# webUSB_V2_combined.net
KiCad netlist of a schematic drawn in EAGLE
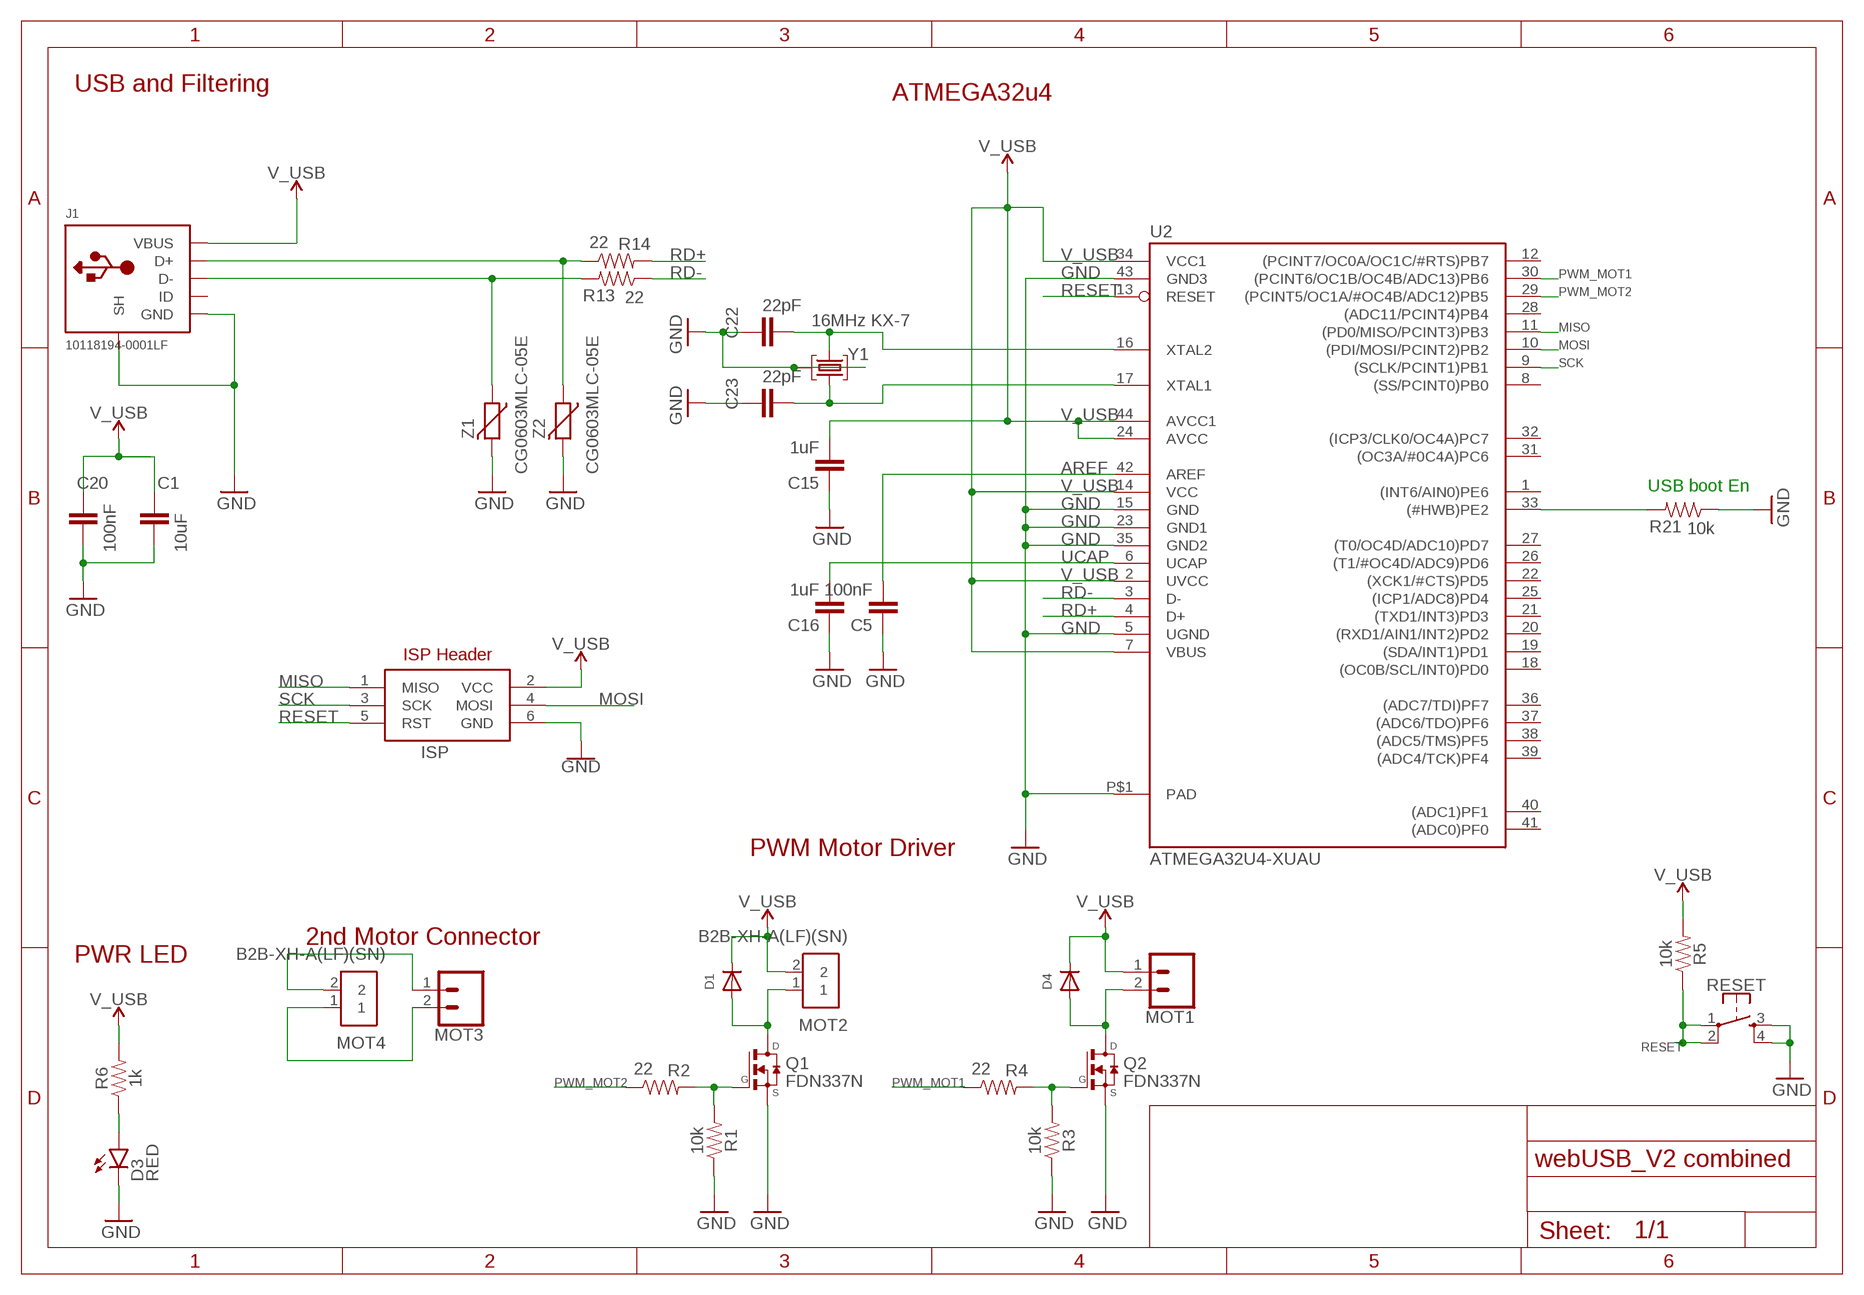
[diagram p0: schematic, sheet 1]

(export (version "E")
  (design (tool "Eeschema 10.0.6"))
  (components
    (comp (ref "C1")
      (value "10uF")
      (footprint "eagle-import:C0805")
      (libsource (lib "eagle-import") (part "CAPACITORSC0805"))
    )
    (comp (ref "C5")
      (value "100nF")
      (footprint "eagle-import:C0603")
      (libsource (lib "eagle-import") (part "My-custom-components_5707583_CAPACITORSC0603"))
    )
    (comp (ref "C15")
      (value "1uF")
      (footprint "eagle-import:C0603")
      (libsource (lib "eagle-import") (part "My-custom-components_5707583_CAPACITORSC0603"))
    )
    (comp (ref "C16")
      (value "1uF")
      (footprint "eagle-import:C0603")
      (libsource (lib "eagle-import") (part "My-custom-components_5707583_CAPACITORSC0603"))
    )
    (comp (ref "C20")
      (value "100nF")
      (footprint "eagle-import:C0603")
      (libsource (lib "eagle-import") (part "CAPACITORSC0603"))
    )
    (comp (ref "C22")
      (value "22pF")
      (footprint "eagle-import:C0603")
      (libsource (lib "eagle-import") (part "My-custom-components_5707583_CAPACITORSC0603"))
    )
    (comp (ref "C23")
      (value "22pF")
      (footprint "eagle-import:C0603")
      (libsource (lib "eagle-import") (part "My-custom-components_5707583_CAPACITORSC0603"))
    )
    (comp (ref "D1")
      (value "DIODESOD-123")
      (footprint "eagle-import:SOD-123")
      (libsource (lib "eagle-import") (part "DIODESOD-123"))
    )
    (comp (ref "D3")
      (value "RED")
      (footprint "eagle-import:LED-0603")
      (libsource (lib "eagle-import") (part "LED-RED0603"))
    )
    (comp (ref "D4")
      (value "DIODESOD-123")
      (footprint "eagle-import:SOD-123")
      (libsource (lib "eagle-import") (part "DIODESOD-123"))
    )
    (comp (ref "ISP")
      (value "AVRISP-6")
      (footprint "eagle-import:AVRISP")
      (libsource (lib "eagle-import") (part "AVRISP-6"))
    )
    (comp (ref "J1")
      (value "10118194-0001LF")
      (footprint "eagle-import:FRAMATOME_10118194-0001LF")
      (fields (field (name "MF") "Amphenol"))
      (libsource (lib "eagle-import") (part "10118194-0001LF"))
    )
    (comp (ref "MOT1")
      (value "CONN_02")
      (footprint "eagle-import:1X02")
      (libsource (lib "eagle-import") (part "CONN_02"))
    )
    (comp (ref "MOT2")
      (value "B2B-XH-A(LF)(SN)")
      (footprint "eagle-import:SHDR2W64P0X250_1X2_740X575X700")
      (fields (field (name "RS_PART_NUMBER") "1667312"))
      (libsource (lib "eagle-import") (part "B2B-XH-A(LF)(SN)"))
    )
    (comp (ref "MOT3")
      (value "CONN_02")
      (footprint "eagle-import:1X02")
      (libsource (lib "eagle-import") (part "CONN_02"))
    )
    (comp (ref "MOT4")
      (value "B2B-XH-A(LF)(SN)")
      (footprint "eagle-import:SHDR2W64P0X250_1X2_740X575X700")
      (fields (field (name "RS_PART_NUMBER") "1667312"))
      (libsource (lib "eagle-import") (part "B2B-XH-A(LF)(SN)"))
    )
    (comp (ref "Q1")
      (value "FDN337N")
      (footprint "eagle-import:SSOT-3")
      (fields (field (name "MF") "ON Semiconductor"))
      (libsource (lib "eagle-import") (part "FDN337N"))
    )
    (comp (ref "Q2")
      (value "FDN337N")
      (footprint "eagle-import:SSOT-3")
      (fields (field (name "MF") "ON Semiconductor"))
      (libsource (lib "eagle-import") (part "FDN337N"))
    )
    (comp (ref "R1")
      (value "10k")
      (footprint "eagle-import:R0603")
      (libsource (lib "eagle-import") (part "RESISTORSR0603"))
    )
    (comp (ref "R2")
      (value "22")
      (footprint "eagle-import:R0603")
      (libsource (lib "eagle-import") (part "RESISTORSR0603"))
    )
    (comp (ref "R3")
      (value "10k")
      (footprint "eagle-import:R0603")
      (libsource (lib "eagle-import") (part "RESISTORSR0603"))
    )
    (comp (ref "R4")
      (value "22")
      (footprint "eagle-import:R0603")
      (libsource (lib "eagle-import") (part "RESISTORSR0603"))
    )
    (comp (ref "R5")
      (value "10k")
      (footprint "eagle-import:R0603")
      (libsource (lib "eagle-import") (part "RESISTORSR0603"))
    )
    (comp (ref "R6")
      (value "1k")
      (footprint "eagle-import:R0603")
      (libsource (lib "eagle-import") (part "RESISTORSR0603"))
    )
    (comp (ref "R13")
      (value "22")
      (footprint "eagle-import:R0603")
      (libsource (lib "eagle-import") (part "RESISTORSR0603"))
    )
    (comp (ref "R14")
      (value "22")
      (footprint "eagle-import:R0603")
      (libsource (lib "eagle-import") (part "RESISTORSR0603"))
    )
    (comp (ref "R21")
      (value "10k")
      (footprint "eagle-import:R0603")
      (libsource (lib "eagle-import") (part "My-custom-components_5707583_RESISTORSR0603"))
    )
    (comp (ref "RESET")
      (value "TACTILE_BUTTON_PTS810")
      (footprint "eagle-import:PTS810")
      (libsource (lib "eagle-import") (part "TACTILE_BUTTON_PTS810"))
    )
    (comp (ref "U2")
      (value "ATMEGA32U4-XUAU")
      (footprint "eagle-import:TQFP44-PAD")
      (libsource (lib "eagle-import") (part "ATMEGA32U4-XUAU"))
    )
    (comp (ref "Y1")
      (value "16MHz KX-7")
      (footprint "eagle-import:CRYSTAL-3.2-2.5")
      (libsource (lib "eagle-import") (part "CRYSTAL-3.2-2.5"))
    )
    (comp (ref "Z1")
      (value "CG0603MLC-05E")
      (footprint "eagle-import:CT_CN0603")
      (libsource (lib "eagle-import") (part "VARISTORCN0603"))
    )
    (comp (ref "Z2")
      (value "CG0603MLC-05E")
      (footprint "eagle-import:CT_CN0603")
      (libsource (lib "eagle-import") (part "VARISTORCN0603"))
    )
  )
  (nets
    (net (code "1") (name "/AREF") (class "Default")
      (node (ref "C5") (pin "2") (pinfunction "2_2") (pintype "passive"))
      (node (ref "U2") (pin "42") (pinfunction "AREF_42") (pintype "power_in"))
    )
    (net (code "2") (name "/RD+") (class "Default")
      (node (ref "R14") (pin "2") (pinfunction "2_2") (pintype "passive"))
      (node (ref "U2") (pin "4") (pinfunction "D+_4") (pintype "bidirectional"))
    )
    (net (code "3") (name "/RD-") (class "Default")
      (node (ref "R13") (pin "1") (pinfunction "1_1") (pintype "passive"))
      (node (ref "U2") (pin "3") (pinfunction "D-_3") (pintype "bidirectional"))
    )
    (net (code "4") (name "/UCAP") (class "Default")
      (node (ref "C16") (pin "2") (pinfunction "2_2") (pintype "passive"))
      (node (ref "U2") (pin "6") (pinfunction "UCAP_6") (pintype "passive"))
    )
    (net (code "5") (name "GND") (class "Default")
      (node (ref "C1") (pin "1") (pinfunction "1_1") (pintype "passive"))
      (node (ref "C15") (pin "1") (pinfunction "1_1") (pintype "passive"))
      (node (ref "C16") (pin "1") (pinfunction "1_1") (pintype "passive"))
      (node (ref "C20") (pin "1") (pinfunction "1_1") (pintype "passive"))
      (node (ref "C22") (pin "2") (pinfunction "2_2") (pintype "passive"))
      (node (ref "C23") (pin "2") (pinfunction "2_2") (pintype "passive"))
      (node (ref "C5") (pin "1") (pinfunction "1_1") (pintype "passive"))
      (node (ref "D3") (pin "C") (pinfunction "C_C") (pintype "passive"))
      (node (ref "ISP") (pin "6") (pinfunction "GND_6") (pintype "power_in"))
      (node (ref "J1") (pin "GND") (pinfunction "GND_GND") (pintype "power_in"))
      (node (ref "J1") (pin "SH1") (pinfunction "SH_SH1") (pintype "power_in"))
      (node (ref "J1") (pin "SH2") (pinfunction "SH_SH2") (pintype "power_in"))
      (node (ref "J1") (pin "SH3") (pinfunction "SH_SH3") (pintype "power_in"))
      (node (ref "J1") (pin "SH4") (pinfunction "SH_SH4") (pintype "power_in"))
      (node (ref "J1") (pin "SH5") (pinfunction "SH_SH5") (pintype "power_in"))
      (node (ref "J1") (pin "SH6") (pinfunction "SH_SH6") (pintype "power_in"))
      (node (ref "J1") (pin "SH7") (pinfunction "SH_SH7") (pintype "power_in"))
      (node (ref "J1") (pin "SH8") (pinfunction "SH_SH8") (pintype "power_in"))
      (node (ref "Q1") (pin "2") (pinfunction "S_2") (pintype "passive"))
      (node (ref "Q2") (pin "2") (pinfunction "S_2") (pintype "passive"))
      (node (ref "R1") (pin "1") (pinfunction "1_1") (pintype "passive"))
      (node (ref "R21") (pin "1") (pinfunction "1_1") (pintype "passive"))
      (node (ref "R3") (pin "1") (pinfunction "1_1") (pintype "passive"))
      (node (ref "RESET") (pin "3") (pinfunction "3_3") (pintype "passive"))
      (node (ref "RESET") (pin "4") (pinfunction "4_4") (pintype "passive"))
      (node (ref "U2") (pin "15") (pinfunction "GND_15") (pintype "power_in"))
      (node (ref "U2") (pin "23") (pinfunction "GND1_23") (pintype "power_in"))
      (node (ref "U2") (pin "35") (pinfunction "GND2_35") (pintype "power_in"))
      (node (ref "U2") (pin "43") (pinfunction "GND3_43") (pintype "power_in"))
      (node (ref "U2") (pin "5") (pinfunction "UGND_5") (pintype "power_in"))
      (node (ref "U2") (pin "P$1") (pinfunction "PAD_P$1") (pintype "power_in"))
      (node (ref "Y1") (pin "2") (pinfunction "GND_2") (pintype "passive"))
      (node (ref "Y1") (pin "4") (pinfunction "GND_4") (pintype "passive"))
      (node (ref "Z1") (pin "2") (pinfunction "2_2") (pintype "passive"))
      (node (ref "Z2") (pin "2") (pinfunction "2_2") (pintype "passive"))
    )
    (net (code "6") (name "MISO") (class "Default")
      (node (ref "ISP") (pin "1") (pinfunction "MISO_1") (pintype "input"))
      (node (ref "U2") (pin "11") (pinfunction "(PD0/MISO/PCINT3)PB3_11") (pintype "bidirectional"))
    )
    (net (code "7") (name "MOSI") (class "Default")
      (node (ref "ISP") (pin "4") (pinfunction "MOSI_4") (pintype "output"))
      (node (ref "U2") (pin "10") (pinfunction "(PDI/MOSI/PCINT2)PB2_10") (pintype "bidirectional"))
    )
    (net (code "8") (name "Net-(D3-PadA)") (class "Default")
      (node (ref "D3") (pin "A") (pinfunction "A_A") (pintype "passive"))
      (node (ref "R6") (pin "1") (pinfunction "1_1") (pintype "passive"))
    )
    (net (code "9") (name "Net-(J1-PadD+)") (class "Default")
      (node (ref "J1") (pin "D+") (pinfunction "D+_D+") (pintype "bidirectional"))
      (node (ref "R14") (pin "1") (pinfunction "1_1") (pintype "passive"))
      (node (ref "Z2") (pin "1") (pinfunction "1_1") (pintype "passive"))
    )
    (net (code "10") (name "Net-(J1-PadD-)") (class "Default")
      (node (ref "J1") (pin "D-") (pinfunction "D-_D-") (pintype "bidirectional"))
      (node (ref "R13") (pin "2") (pinfunction "2_2") (pintype "passive"))
      (node (ref "Z1") (pin "1") (pinfunction "1_1") (pintype "passive"))
    )
    (net (code "11") (name "Net-(MOT3-Pad1)") (class "Default")
      (node (ref "MOT3") (pin "1") (pinfunction "1_1") (pintype "passive"))
      (node (ref "MOT4") (pin "2") (pinfunction "2_2") (pintype "bidirectional"))
    )
    (net (code "12") (name "Net-(MOT3-Pad2)") (class "Default")
      (node (ref "MOT3") (pin "2") (pinfunction "2_2") (pintype "passive"))
      (node (ref "MOT4") (pin "1") (pinfunction "1_1") (pintype "bidirectional"))
    )
    (net (code "13") (name "Net-(Q1-D)") (class "Default")
      (node (ref "D1") (pin "A") (pinfunction "A_A") (pintype "passive"))
      (node (ref "MOT2") (pin "1") (pinfunction "1_1") (pintype "bidirectional"))
      (node (ref "Q1") (pin "3") (pinfunction "D_3") (pintype "passive"))
    )
    (net (code "14") (name "Net-(Q1-G)") (class "Default")
      (node (ref "Q1") (pin "1") (pinfunction "G_1") (pintype "passive"))
      (node (ref "R1") (pin "2") (pinfunction "2_2") (pintype "passive"))
      (node (ref "R2") (pin "2") (pinfunction "2_2") (pintype "passive"))
    )
    (net (code "15") (name "Net-(Q2-D)") (class "Default")
      (node (ref "D4") (pin "A") (pinfunction "A_A") (pintype "passive"))
      (node (ref "MOT1") (pin "2") (pinfunction "2_2") (pintype "passive"))
      (node (ref "Q2") (pin "3") (pinfunction "D_3") (pintype "passive"))
    )
    (net (code "16") (name "Net-(Q2-G)") (class "Default")
      (node (ref "Q2") (pin "1") (pinfunction "G_1") (pintype "passive"))
      (node (ref "R3") (pin "2") (pinfunction "2_2") (pintype "passive"))
      (node (ref "R4") (pin "2") (pinfunction "2_2") (pintype "passive"))
    )
    (net (code "17") (name "Net-(U2-(#HWB)PE2)") (class "Default")
      (node (ref "R21") (pin "2") (pinfunction "2_2") (pintype "passive"))
      (node (ref "U2") (pin "33") (pinfunction "(#HWB)PE2_33") (pintype "bidirectional"))
    )
    (net (code "18") (name "Net-(U2-XTAL1)") (class "Default")
      (node (ref "C23") (pin "1") (pinfunction "1_1") (pintype "passive"))
      (node (ref "U2") (pin "17") (pinfunction "XTAL1_17") (pintype "bidirectional"))
      (node (ref "Y1") (pin "1") (pinfunction "C1_1") (pintype "passive"))
    )
    (net (code "19") (name "Net-(U2-XTAL2)") (class "Default")
      (node (ref "C22") (pin "1") (pinfunction "1_1") (pintype "passive"))
      (node (ref "U2") (pin "16") (pinfunction "XTAL2_16") (pintype "bidirectional"))
      (node (ref "Y1") (pin "3") (pinfunction "C2_3") (pintype "passive"))
    )
    (net (code "20") (name "PWM_MOT1") (class "Default")
      (node (ref "R4") (pin "1") (pinfunction "1_1") (pintype "passive"))
      (node (ref "U2") (pin "30") (pinfunction "(PCINT6/OC1B/OC4B/ADC13)PB6_30") (pintype "bidirectional"))
    )
    (net (code "21") (name "PWM_MOT2") (class "Default")
      (node (ref "R2") (pin "1") (pinfunction "1_1") (pintype "passive"))
      (node (ref "U2") (pin "29") (pinfunction "(PCINT5/OC1A/#OC4B/ADC12)PB5_29") (pintype "bidirectional"))
    )
    (net (code "22") (name "RESET") (class "Default")
      (node (ref "ISP") (pin "5") (pinfunction "RST_5") (pintype "output"))
      (node (ref "R5") (pin "1") (pinfunction "1_1") (pintype "passive"))
      (node (ref "RESET") (pin "1") (pinfunction "1_1") (pintype "passive"))
      (node (ref "RESET") (pin "2") (pinfunction "2_2") (pintype "passive"))
      (node (ref "U2") (pin "13") (pinfunction "RESET_13") (pintype "input"))
    )
    (net (code "23") (name "SCK") (class "Default")
      (node (ref "ISP") (pin "3") (pinfunction "SCK_3") (pintype "output"))
      (node (ref "U2") (pin "9") (pinfunction "(SCLK/PCINT1)PB1_9") (pintype "bidirectional"))
    )
    (net (code "24") (name "V_USB") (class "Default")
      (node (ref "C1") (pin "2") (pinfunction "2_2") (pintype "passive"))
      (node (ref "C15") (pin "2") (pinfunction "2_2") (pintype "passive"))
      (node (ref "C20") (pin "2") (pinfunction "2_2") (pintype "passive"))
      (node (ref "D1") (pin "C") (pinfunction "C_C") (pintype "passive"))
      (node (ref "D4") (pin "C") (pinfunction "C_C") (pintype "passive"))
      (node (ref "ISP") (pin "2") (pinfunction "VCC_2") (pintype "power_in"))
      (node (ref "J1") (pin "VUSB") (pinfunction "VBUS_VUSB") (pintype "power_in"))
      (node (ref "MOT1") (pin "1") (pinfunction "1_1") (pintype "passive"))
      (node (ref "MOT2") (pin "2") (pinfunction "2_2") (pintype "bidirectional"))
      (node (ref "R5") (pin "2") (pinfunction "2_2") (pintype "passive"))
      (node (ref "R6") (pin "2") (pinfunction "2_2") (pintype "passive"))
      (node (ref "U2") (pin "14") (pinfunction "VCC_14") (pintype "power_in"))
      (node (ref "U2") (pin "2") (pinfunction "UVCC_2") (pintype "power_in"))
      (node (ref "U2") (pin "24") (pinfunction "AVCC_24") (pintype "power_in"))
      (node (ref "U2") (pin "34") (pinfunction "VCC1_34") (pintype "power_in"))
      (node (ref "U2") (pin "44") (pinfunction "AVCC1_44") (pintype "power_in"))
      (node (ref "U2") (pin "7") (pinfunction "VBUS_7") (pintype "input"))
    )
    (net (code "25") (name "unconnected-(J1-PadID)") (class "Default")
      (node (ref "J1") (pin "ID") (pinfunction "ID_ID") (pintype "bidirectional"))
    )
    (net (code "26") (name "unconnected-(U2-(ADC0)PF0-Pad41)") (class "Default")
      (node (ref "U2") (pin "41") (pinfunction "(ADC0)PF0_41") (pintype "bidirectional"))
    )
    (net (code "27") (name "unconnected-(U2-(ADC1)PF1-Pad40)") (class "Default")
      (node (ref "U2") (pin "40") (pinfunction "(ADC1)PF1_40") (pintype "bidirectional"))
    )
    (net (code "28") (name "unconnected-(U2-(ADC4{slash}TCK)PF4-Pad39)") (class "Default")
      (node (ref "U2") (pin "39") (pinfunction "(ADC4/TCK)PF4_39") (pintype "bidirectional"))
    )
    (net (code "29") (name "unconnected-(U2-(ADC5{slash}TMS)PF5-Pad38)") (class "Default")
      (node (ref "U2") (pin "38") (pinfunction "(ADC5/TMS)PF5_38") (pintype "bidirectional"))
    )
    (net (code "30") (name "unconnected-(U2-(ADC6{slash}TDO)PF6-Pad37)") (class "Default")
      (node (ref "U2") (pin "37") (pinfunction "(ADC6/TDO)PF6_37") (pintype "bidirectional"))
    )
    (net (code "31") (name "unconnected-(U2-(ADC7{slash}TDI)PF7-Pad36)") (class "Default")
      (node (ref "U2") (pin "36") (pinfunction "(ADC7/TDI)PF7_36") (pintype "bidirectional"))
    )
    (net (code "32") (name "unconnected-(U2-(ADC11{slash}PCINT4)PB4-Pad28)") (class "Default")
      (node (ref "U2") (pin "28") (pinfunction "(ADC11/PCINT4)PB4_28") (pintype "bidirectional"))
    )
    (net (code "33") (name "unconnected-(U2-(ICP1{slash}ADC8)PD4-Pad25)") (class "Default")
      (node (ref "U2") (pin "25") (pinfunction "(ICP1/ADC8)PD4_25") (pintype "bidirectional"))
    )
    (net (code "34") (name "unconnected-(U2-(ICP3{slash}CLK0{slash}OC4A)PC7-Pad32)") (class "Default")
      (node (ref "U2") (pin "32") (pinfunction "(ICP3/CLK0/OC4A)PC7_32") (pintype "bidirectional"))
    )
    (net (code "35") (name "unconnected-(U2-(INT6{slash}AIN0)PE6-Pad1)") (class "Default")
      (node (ref "U2") (pin "1") (pinfunction "(INT6/AIN0)PE6_1") (pintype "bidirectional"))
    )
    (net (code "36") (name "unconnected-(U2-(OC0B{slash}SCL{slash}INT0)PD0-Pad18)") (class "Default")
      (node (ref "U2") (pin "18") (pinfunction "(OC0B/SCL/INT0)PD0_18") (pintype "bidirectional"))
    )
    (net (code "37") (name "unconnected-(U2-(OC3A{slash}#0C4A)PC6-Pad31)") (class "Default")
      (node (ref "U2") (pin "31") (pinfunction "(OC3A/#0C4A)PC6_31") (pintype "bidirectional"))
    )
    (net (code "38") (name "unconnected-(U2-(PCINT7{slash}OC0A{slash}OC1C{slash}#RTS)PB7-Pad12)") (class "Default")
      (node (ref "U2") (pin "12") (pinfunction "(PCINT7/OC0A/OC1C/#RTS)PB7_12") (pintype "bidirectional"))
    )
    (net (code "39") (name "unconnected-(U2-(RXD1{slash}AIN1{slash}INT2)PD2-Pad20)") (class "Default")
      (node (ref "U2") (pin "20") (pinfunction "(RXD1/AIN1/INT2)PD2_20") (pintype "bidirectional"))
    )
    (net (code "40") (name "unconnected-(U2-(SDA{slash}INT1)PD1-Pad19)") (class "Default")
      (node (ref "U2") (pin "19") (pinfunction "(SDA/INT1)PD1_19") (pintype "bidirectional"))
    )
    (net (code "41") (name "unconnected-(U2-(SS{slash}PCINT0)PB0-Pad8)") (class "Default")
      (node (ref "U2") (pin "8") (pinfunction "(SS/PCINT0)PB0_8") (pintype "bidirectional"))
    )
    (net (code "42") (name "unconnected-(U2-(T0{slash}OC4D{slash}ADC10)PD7-Pad27)") (class "Default")
      (node (ref "U2") (pin "27") (pinfunction "(T0/OC4D/ADC10)PD7_27") (pintype "bidirectional"))
    )
    (net (code "43") (name "unconnected-(U2-(T1{slash}#OC4D{slash}ADC9)PD6-Pad26)") (class "Default")
      (node (ref "U2") (pin "26") (pinfunction "(T1/#OC4D/ADC9)PD6_26") (pintype "bidirectional"))
    )
    (net (code "44") (name "unconnected-(U2-(TXD1{slash}INT3)PD3-Pad21)") (class "Default")
      (node (ref "U2") (pin "21") (pinfunction "(TXD1/INT3)PD3_21") (pintype "bidirectional"))
    )
    (net (code "45") (name "unconnected-(U2-(XCK1{slash}#CTS)PD5-Pad22)") (class "Default")
      (node (ref "U2") (pin "22") (pinfunction "(XCK1/#CTS)PD5_22") (pintype "bidirectional"))
    )
  )
)
